# ant1zykl0n.net
KiCad netlist of a schematic drawn in EAGLE
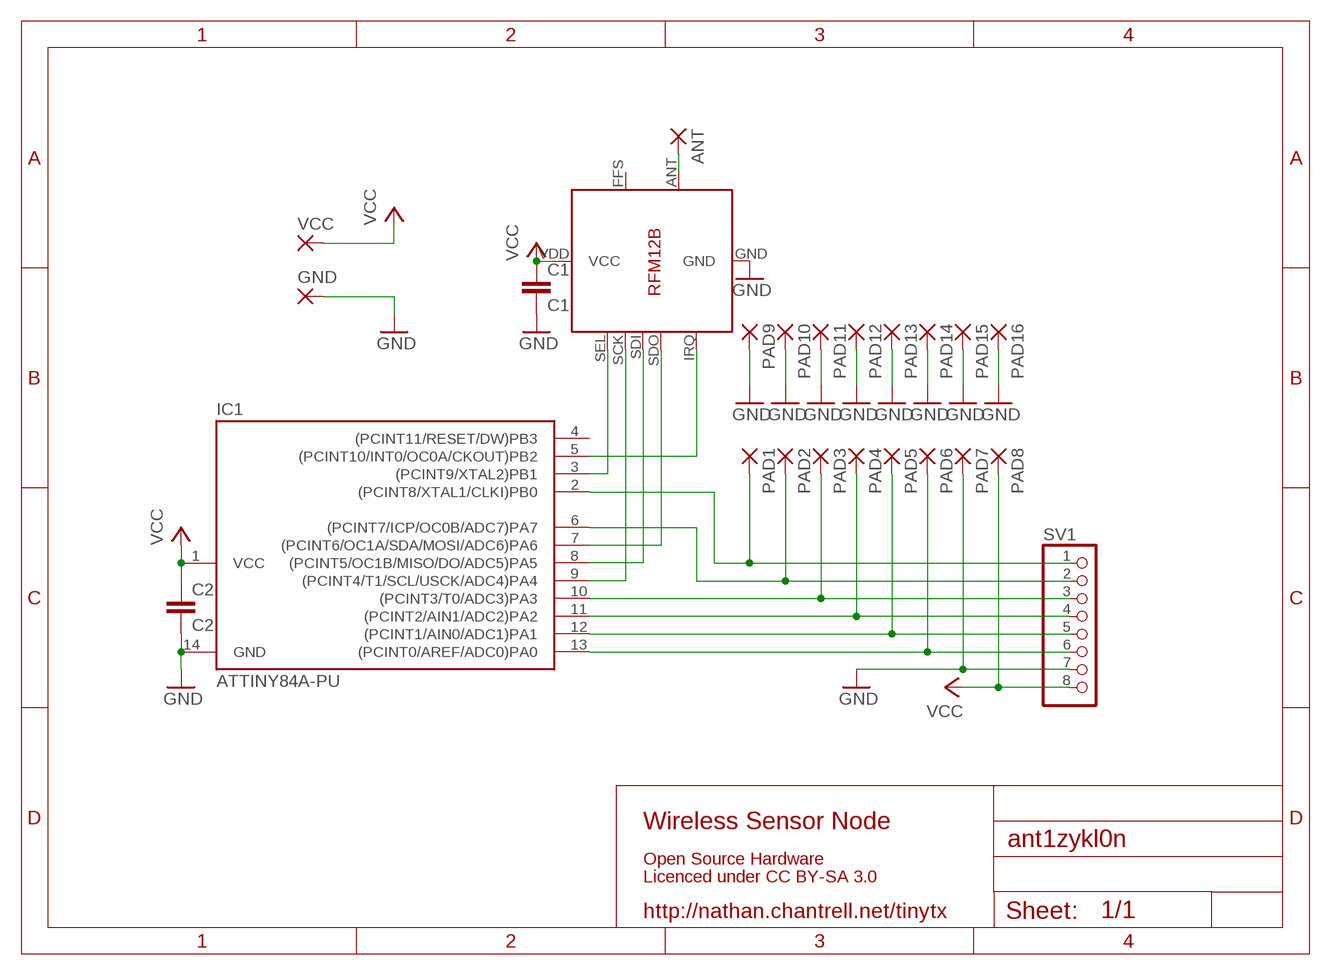
[diagram p0: schematic, sheet 1]

(export (version "E")
  (design (tool "Eeschema 10.0.6"))
  (components
    (comp (ref "ANT")
      (value "2,15/1,0")
      (footprint "eagle-import:2,15_1,0")
      (libsource (lib "eagle-import") (part "wirepad_mod_2,15/1,0"))
    )
    (comp (ref "C1")
      (value "C1")
      (footprint "eagle-import:C025-025X050")
      (libsource (lib "eagle-import") (part "C-EU025-025X050"))
    )
    (comp (ref "C2")
      (value "C2")
      (footprint "eagle-import:C025-025X050")
      (libsource (lib "eagle-import") (part "C-EU025-025X050"))
    )
    (comp (ref "GND")
      (value "2,15/1,0")
      (footprint "eagle-import:2,15_1,0")
      (libsource (lib "eagle-import") (part "2,15/1,0"))
    )
    (comp (ref "IC1")
      (value "ATTINY84A-PU")
      (footprint "eagle-import:DIL14")
      (libsource (lib "eagle-import") (part "TINY24/44/84-PU"))
    )
    (comp (ref "PAD1")
      (value "1,6/0,9")
      (footprint "eagle-import:1,6_0,9")
      (libsource (lib "eagle-import") (part "1,6/0,9"))
    )
    (comp (ref "PAD2")
      (value "1,6/0,9")
      (footprint "eagle-import:1,6_0,9")
      (libsource (lib "eagle-import") (part "1,6/0,9"))
    )
    (comp (ref "PAD3")
      (value "1,6/0,9")
      (footprint "eagle-import:1,6_0,9")
      (libsource (lib "eagle-import") (part "1,6/0,9"))
    )
    (comp (ref "PAD4")
      (value "1,6/0,9")
      (footprint "eagle-import:1,6_0,9")
      (libsource (lib "eagle-import") (part "1,6/0,9"))
    )
    (comp (ref "PAD5")
      (value "1,6/0,9")
      (footprint "eagle-import:1,6_0,9")
      (libsource (lib "eagle-import") (part "1,6/0,9"))
    )
    (comp (ref "PAD6")
      (value "1,6/0,9")
      (footprint "eagle-import:1,6_0,9")
      (libsource (lib "eagle-import") (part "1,6/0,9"))
    )
    (comp (ref "PAD7")
      (value "1,6/0,9")
      (footprint "eagle-import:1,6_0,9")
      (libsource (lib "eagle-import") (part "1,6/0,9"))
    )
    (comp (ref "PAD8")
      (value "1,6/0,9")
      (footprint "eagle-import:1,6_0,9")
      (libsource (lib "eagle-import") (part "1,6/0,9"))
    )
    (comp (ref "PAD9")
      (value "1,6/0,9")
      (footprint "eagle-import:1,6_0,9")
      (libsource (lib "eagle-import") (part "1,6/0,9"))
    )
    (comp (ref "PAD10")
      (value "1,6/0,9")
      (footprint "eagle-import:1,6_0,9")
      (libsource (lib "eagle-import") (part "1,6/0,9"))
    )
    (comp (ref "PAD11")
      (value "1,6/0,9")
      (footprint "eagle-import:1,6_0,9")
      (libsource (lib "eagle-import") (part "1,6/0,9"))
    )
    (comp (ref "PAD12")
      (value "1,6/0,9")
      (footprint "eagle-import:1,6_0,9")
      (libsource (lib "eagle-import") (part "1,6/0,9"))
    )
    (comp (ref "PAD13")
      (value "1,6/0,9")
      (footprint "eagle-import:1,6_0,9")
      (libsource (lib "eagle-import") (part "1,6/0,9"))
    )
    (comp (ref "PAD14")
      (value "1,6/0,9")
      (footprint "eagle-import:1,6_0,9")
      (libsource (lib "eagle-import") (part "1,6/0,9"))
    )
    (comp (ref "PAD15")
      (value "1,6/0,9")
      (footprint "eagle-import:1,6_0,9")
      (libsource (lib "eagle-import") (part "1,6/0,9"))
    )
    (comp (ref "PAD16")
      (value "1,6/0,9")
      (footprint "eagle-import:1,6_0,9")
      (libsource (lib "eagle-import") (part "1,6/0,9"))
    )
    (comp (ref "SV1")
      (value "PINHD-1X8")
      (footprint "eagle-import:1X08")
      (libsource (lib "eagle-import") (part "PINHD-1X8"))
    )
    (comp (ref "U$1")
      (value "RFM12B")
      (footprint "eagle-import:RFM12B")
      (libsource (lib "eagle-import") (part "RFM12B"))
    )
    (comp (ref "VCC")
      (value "2,15/1,0")
      (footprint "eagle-import:2,15_1,0")
      (libsource (lib "eagle-import") (part "2,15/1,0"))
    )
  )
  (nets
    (net (code "1") (name "GND") (class "Default")
      (node (ref "C1") (pin "2") (pinfunction "2_2") (pintype "passive"))
      (node (ref "C2") (pin "2") (pinfunction "2_2") (pintype "passive"))
      (node (ref "GND") (pin "1") (pinfunction "P_1") (pintype "passive"))
      (node (ref "IC1") (pin "14") (pinfunction "GND_14") (pintype "power_in"))
      (node (ref "PAD10") (pin "1") (pinfunction "P_1") (pintype "passive"))
      (node (ref "PAD11") (pin "1") (pinfunction "P_1") (pintype "passive"))
      (node (ref "PAD12") (pin "1") (pinfunction "P_1") (pintype "passive"))
      (node (ref "PAD13") (pin "1") (pinfunction "P_1") (pintype "passive"))
      (node (ref "PAD14") (pin "1") (pinfunction "P_1") (pintype "passive"))
      (node (ref "PAD15") (pin "1") (pinfunction "P_1") (pintype "passive"))
      (node (ref "PAD16") (pin "1") (pinfunction "P_1") (pintype "passive"))
      (node (ref "PAD7") (pin "1") (pinfunction "P_1") (pintype "passive"))
      (node (ref "PAD9") (pin "1") (pinfunction "P_1") (pintype "passive"))
      (node (ref "SV1") (pin "7") (pinfunction "7_7") (pintype "passive"))
      (node (ref "U$1") (pin "GND") (pinfunction "GND_GND") (pintype "power_in"))
    )
    (net (code "2") (name "Net-(ANT-P)") (class "Default")
      (node (ref "ANT") (pin "1") (pinfunction "P_1") (pintype "passive"))
      (node (ref "U$1") (pin "ANT") (pinfunction "ANT_ANT") (pintype "passive"))
    )
    (net (code "3") (name "Net-(IC1-(PCINT0{slash}AREF{slash}ADC0)PA0)") (class "Default")
      (node (ref "IC1") (pin "13") (pinfunction "(PCINT0/AREF/ADC0)PA0_13") (pintype "bidirectional"))
      (node (ref "PAD6") (pin "1") (pinfunction "P_1") (pintype "passive"))
      (node (ref "SV1") (pin "6") (pinfunction "6_6") (pintype "passive"))
    )
    (net (code "4") (name "Net-(IC1-(PCINT1{slash}AIN0{slash}ADC1)PA1)") (class "Default")
      (node (ref "IC1") (pin "12") (pinfunction "(PCINT1/AIN0/ADC1)PA1_12") (pintype "bidirectional"))
      (node (ref "PAD5") (pin "1") (pinfunction "P_1") (pintype "passive"))
      (node (ref "SV1") (pin "5") (pinfunction "5_5") (pintype "passive"))
    )
    (net (code "5") (name "Net-(IC1-(PCINT2{slash}AIN1{slash}ADC2)PA2)") (class "Default")
      (node (ref "IC1") (pin "11") (pinfunction "(PCINT2/AIN1/ADC2)PA2_11") (pintype "bidirectional"))
      (node (ref "PAD4") (pin "1") (pinfunction "P_1") (pintype "passive"))
      (node (ref "SV1") (pin "4") (pinfunction "4_4") (pintype "passive"))
    )
    (net (code "6") (name "Net-(IC1-(PCINT3{slash}T0{slash}ADC3)PA3)") (class "Default")
      (node (ref "IC1") (pin "10") (pinfunction "(PCINT3/T0/ADC3)PA3_10") (pintype "bidirectional"))
      (node (ref "PAD3") (pin "1") (pinfunction "P_1") (pintype "passive"))
      (node (ref "SV1") (pin "3") (pinfunction "3_3") (pintype "passive"))
    )
    (net (code "7") (name "Net-(IC1-(PCINT4{slash}T1{slash}SCL{slash}USCK{slash}ADC4)PA4)") (class "Default")
      (node (ref "IC1") (pin "9") (pinfunction "(PCINT4/T1/SCL/USCK/ADC4)PA4_9") (pintype "bidirectional"))
      (node (ref "U$1") (pin "SCK") (pinfunction "SCK_SCK") (pintype "input"))
    )
    (net (code "8") (name "Net-(IC1-(PCINT5{slash}OC1B{slash}MISO{slash}DO{slash}ADC5)PA5)") (class "Default")
      (node (ref "IC1") (pin "8") (pinfunction "(PCINT5/OC1B/MISO/DO/ADC5)PA5_8") (pintype "bidirectional"))
      (node (ref "U$1") (pin "SDI") (pinfunction "SDI_SDI") (pintype "input"))
    )
    (net (code "9") (name "Net-(IC1-(PCINT6{slash}OC1A{slash}SDA{slash}MOSI{slash}ADC6)PA6)") (class "Default")
      (node (ref "IC1") (pin "7") (pinfunction "(PCINT6/OC1A/SDA/MOSI/ADC6)PA6_7") (pintype "bidirectional"))
      (node (ref "U$1") (pin "SDO") (pinfunction "SDO_SDO") (pintype "output"))
    )
    (net (code "10") (name "Net-(IC1-(PCINT7{slash}ICP{slash}OC0B{slash}ADC7)PA7)") (class "Default")
      (node (ref "IC1") (pin "6") (pinfunction "(PCINT7/ICP/OC0B/ADC7)PA7_6") (pintype "bidirectional"))
      (node (ref "PAD2") (pin "1") (pinfunction "P_1") (pintype "passive"))
      (node (ref "SV1") (pin "2") (pinfunction "2_2") (pintype "passive"))
    )
    (net (code "11") (name "Net-(IC1-(PCINT8{slash}XTAL1{slash}CLKI)PB0)") (class "Default")
      (node (ref "IC1") (pin "2") (pinfunction "(PCINT8/XTAL1/CLKI)PB0_2") (pintype "bidirectional"))
      (node (ref "PAD1") (pin "1") (pinfunction "P_1") (pintype "passive"))
      (node (ref "SV1") (pin "1") (pinfunction "1_1") (pintype "passive"))
    )
    (net (code "12") (name "Net-(IC1-(PCINT9{slash}XTAL2)PB1)") (class "Default")
      (node (ref "IC1") (pin "3") (pinfunction "(PCINT9/XTAL2)PB1_3") (pintype "bidirectional"))
      (node (ref "U$1") (pin "SEL") (pinfunction "SEL_SEL") (pintype "input"))
    )
    (net (code "13") (name "Net-(IC1-(PCINT10{slash}INT0{slash}OC0A{slash}CKOUT)PB2)") (class "Default")
      (node (ref "IC1") (pin "5") (pinfunction "(PCINT10/INT0/OC0A/CKOUT)PB2_5") (pintype "bidirectional"))
      (node (ref "U$1") (pin "IRQ") (pinfunction "IRQ_IRQ") (pintype "open_collector"))
    )
    (net (code "14") (name "VCC") (class "Default")
      (node (ref "C1") (pin "1") (pinfunction "1_1") (pintype "passive"))
      (node (ref "C2") (pin "1") (pinfunction "1_1") (pintype "passive"))
      (node (ref "IC1") (pin "1") (pinfunction "VCC_1") (pintype "power_in"))
      (node (ref "PAD8") (pin "1") (pinfunction "P_1") (pintype "passive"))
      (node (ref "SV1") (pin "8") (pinfunction "8_8") (pintype "passive"))
      (node (ref "U$1") (pin "VDD") (pinfunction "VCC_VDD") (pintype "power_in"))
      (node (ref "VCC") (pin "1") (pinfunction "P_1") (pintype "passive"))
    )
    (net (code "15") (name "unconnected-(IC1-(PCINT11{slash}RESET{slash}DW)PB3-Pad4)") (class "Default")
      (node (ref "IC1") (pin "4") (pinfunction "(PCINT11/RESET/DW)PB3_4") (pintype "bidirectional"))
    )
    (net (code "16") (name "unconnected-(U$1-PadFFS)") (class "Default")
      (node (ref "U$1") (pin "FFS") (pinfunction "FFS_FFS") (pintype "bidirectional"))
    )
  )
)
